# turbosound28p.net
KiCad netlist of a schematic drawn in EAGLE
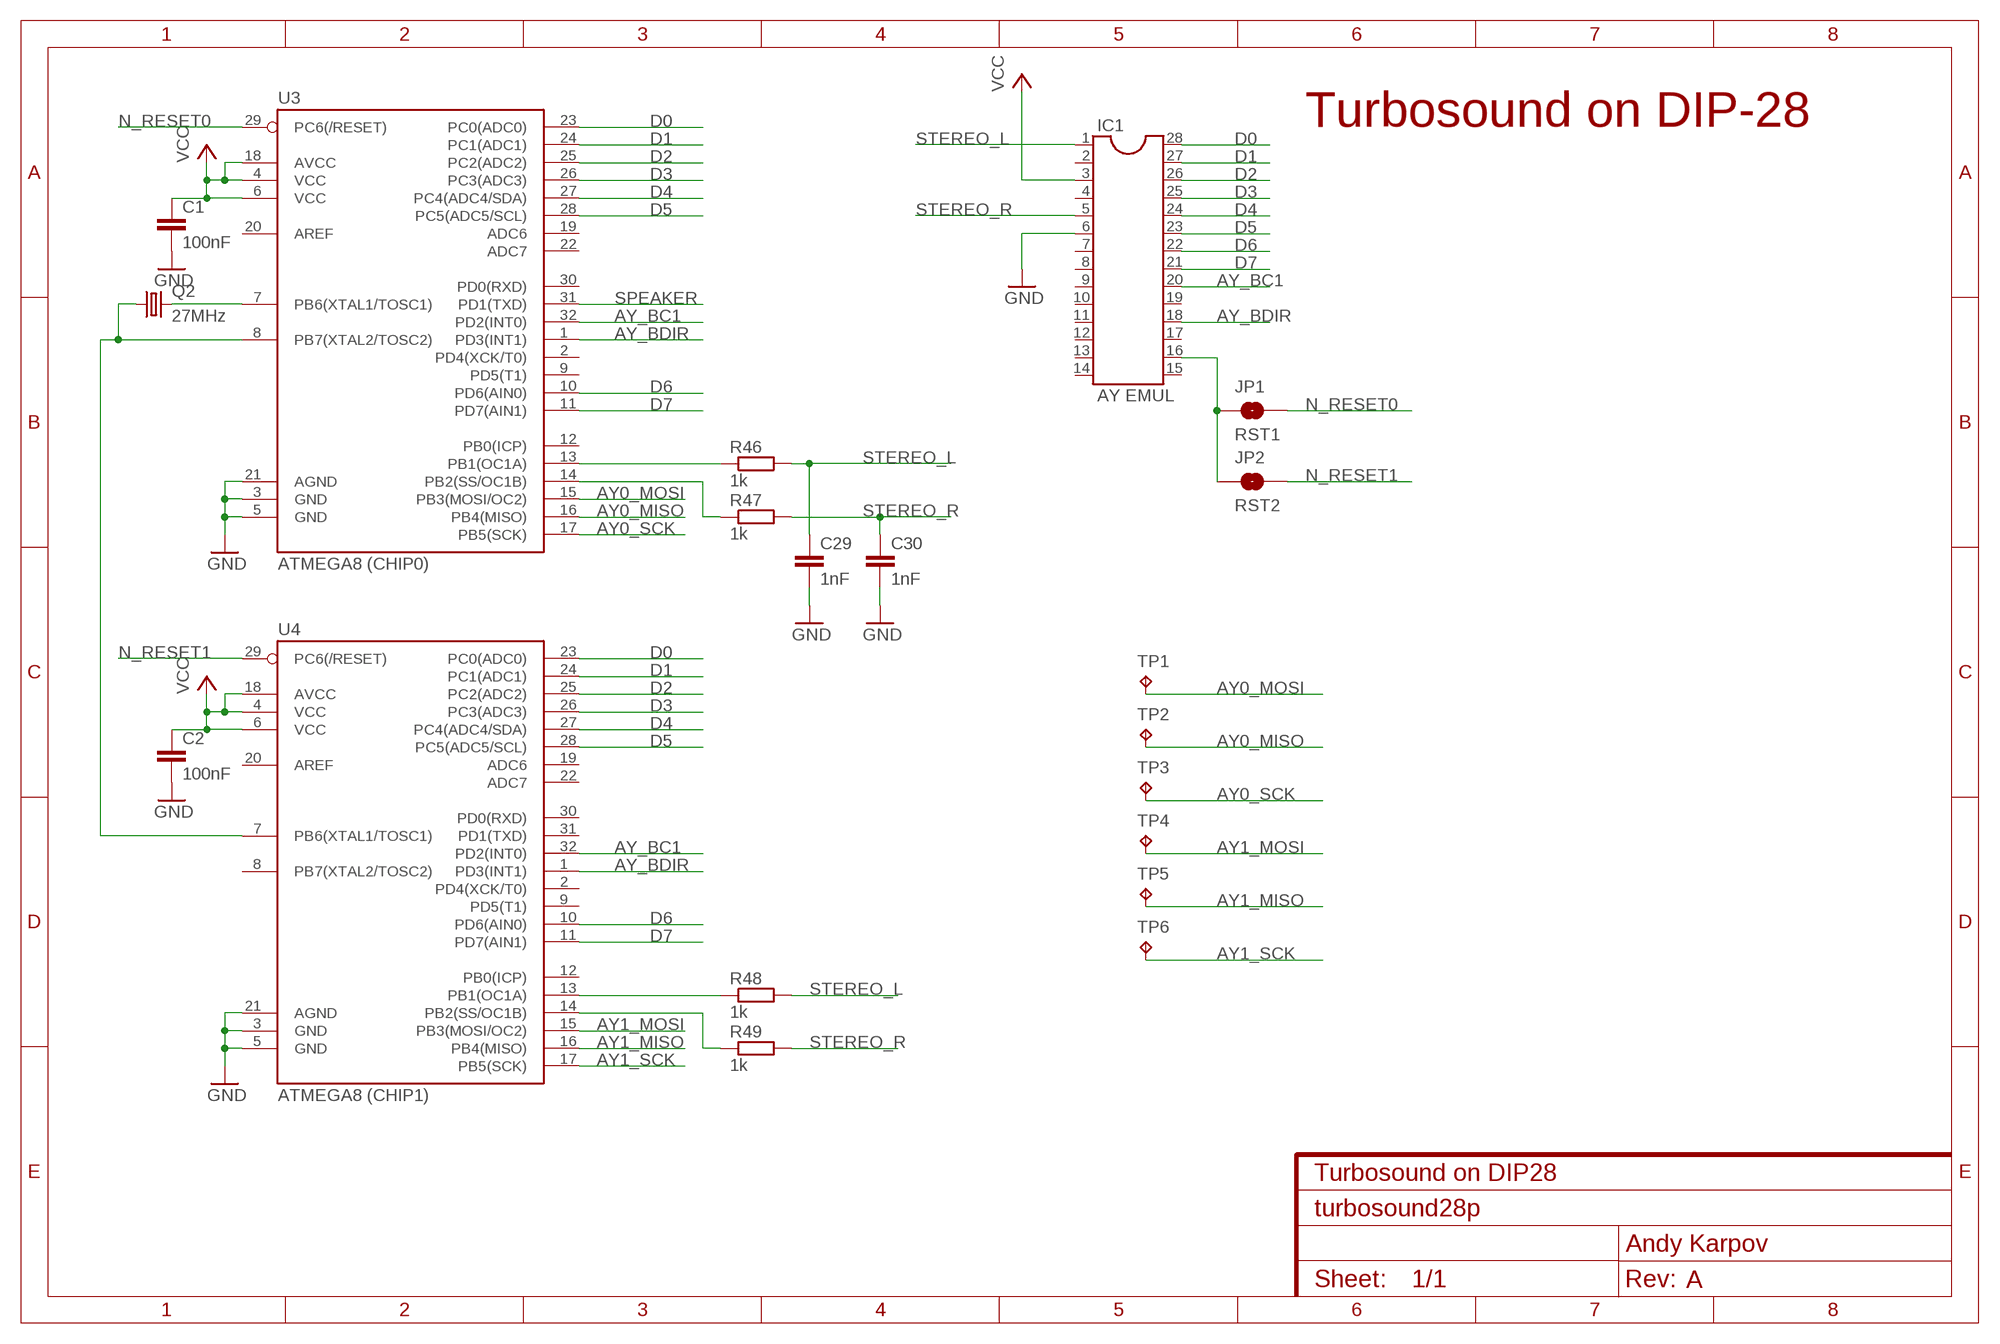
[diagram p0: schematic, sheet 1]

(export (version "E")
  (design (tool "Eeschema 10.0.6"))
  (components
    (comp (ref "C1")
      (value "100nF")
      (footprint "eagle-import:C0805")
      (libsource (lib "eagle-import") (part "C-EUC0805"))
    )
    (comp (ref "C2")
      (value "100nF")
      (footprint "eagle-import:C0805")
      (libsource (lib "eagle-import") (part "C-EUC0805"))
    )
    (comp (ref "C29")
      (value "1nF")
      (footprint "eagle-import:C0805")
      (libsource (lib "eagle-import") (part "C-EUC0805"))
    )
    (comp (ref "C30")
      (value "1nF")
      (footprint "eagle-import:C0805")
      (libsource (lib "eagle-import") (part "C-EUC0805"))
    )
    (comp (ref "IC1")
      (value "AY EMUL")
      (footprint "eagle-import:DIL28-6")
      (libsource (lib "eagle-import") (part "DIL28"))
    )
    (comp (ref "JP1")
      (value "RST1")
      (footprint "eagle-import:SMT-JUMPER_2_NO_SILK")
      (libsource (lib "eagle-import") (part "JUMPER-SMT_2_NO_SILK"))
    )
    (comp (ref "JP2")
      (value "RST2")
      (footprint "eagle-import:SMT-JUMPER_2_NO_SILK")
      (libsource (lib "eagle-import") (part "JUMPER-SMT_2_NO_SILK"))
    )
    (comp (ref "Q2")
      (value "27MHz")
      (footprint "eagle-import:HC49_S")
      (libsource (lib "eagle-import") (part "CRYSTALHC49S"))
    )
    (comp (ref "R46")
      (value "1k")
      (footprint "eagle-import:R0805")
      (libsource (lib "eagle-import") (part "R-EU_R0805"))
    )
    (comp (ref "R47")
      (value "1k")
      (footprint "eagle-import:R0805")
      (libsource (lib "eagle-import") (part "R-EU_R0805"))
    )
    (comp (ref "R48")
      (value "1k")
      (footprint "eagle-import:R0805")
      (libsource (lib "eagle-import") (part "R-EU_R0805"))
    )
    (comp (ref "R49")
      (value "1k")
      (footprint "eagle-import:R0805")
      (libsource (lib "eagle-import") (part "R-EU_R0805"))
    )
    (comp (ref "TP1")
      (value "TPB1,27")
      (footprint "eagle-import:B1,27")
      (libsource (lib "eagle-import") (part "TPB1,27"))
    )
    (comp (ref "TP2")
      (value "TPB1,27")
      (footprint "eagle-import:B1,27")
      (libsource (lib "eagle-import") (part "TPB1,27"))
    )
    (comp (ref "TP3")
      (value "TPB1,27")
      (footprint "eagle-import:B1,27")
      (libsource (lib "eagle-import") (part "TPB1,27"))
    )
    (comp (ref "TP4")
      (value "TPB1,27")
      (footprint "eagle-import:B1,27")
      (libsource (lib "eagle-import") (part "TPB1,27"))
    )
    (comp (ref "TP5")
      (value "TPB1,27")
      (footprint "eagle-import:B1,27")
      (libsource (lib "eagle-import") (part "TPB1,27"))
    )
    (comp (ref "TP6")
      (value "TPB1,27")
      (footprint "eagle-import:B1,27")
      (libsource (lib "eagle-import") (part "TPB1,27"))
    )
    (comp (ref "U3")
      (value "ATMEGA8 (CHIP0)")
      (footprint "eagle-import:TQFP32-08")
      (libsource (lib "eagle-import") (part "ATMEGA328P_TQFP"))
    )
    (comp (ref "U4")
      (value "ATMEGA8 (CHIP1)")
      (footprint "eagle-import:TQFP32-08")
      (libsource (lib "eagle-import") (part "ATMEGA328P_TQFP"))
    )
  )
  (nets
    (net (code "1") (name "/AY0_MISO") (class "Default")
      (node (ref "TP2") (pin "TP") (pinfunction "TP_TP") (pintype "input"))
      (node (ref "U3") (pin "16") (pinfunction "PB4(MISO)_16") (pintype "bidirectional"))
    )
    (net (code "2") (name "/AY0_MOSI") (class "Default")
      (node (ref "TP1") (pin "TP") (pinfunction "TP_TP") (pintype "input"))
      (node (ref "U3") (pin "15") (pinfunction "PB3(MOSI/OC2)_15") (pintype "bidirectional"))
    )
    (net (code "3") (name "/AY0_SCK") (class "Default")
      (node (ref "TP3") (pin "TP") (pinfunction "TP_TP") (pintype "input"))
      (node (ref "U3") (pin "17") (pinfunction "PB5(SCK)_17") (pintype "bidirectional"))
    )
    (net (code "4") (name "/AY1_MISO") (class "Default")
      (node (ref "TP5") (pin "TP") (pinfunction "TP_TP") (pintype "input"))
      (node (ref "U4") (pin "16") (pinfunction "PB4(MISO)_16") (pintype "bidirectional"))
    )
    (net (code "5") (name "/AY1_MOSI") (class "Default")
      (node (ref "TP4") (pin "TP") (pinfunction "TP_TP") (pintype "input"))
      (node (ref "U4") (pin "15") (pinfunction "PB3(MOSI/OC2)_15") (pintype "bidirectional"))
    )
    (net (code "6") (name "/AY1_SCK") (class "Default")
      (node (ref "TP6") (pin "TP") (pinfunction "TP_TP") (pintype "input"))
      (node (ref "U4") (pin "17") (pinfunction "PB5(SCK)_17") (pintype "bidirectional"))
    )
    (net (code "7") (name "/AY_BC1") (class "Default")
      (node (ref "IC1") (pin "20") (pinfunction "20_20") (pintype "passive"))
      (node (ref "U3") (pin "32") (pinfunction "PD2(INT0)_32") (pintype "bidirectional"))
      (node (ref "U4") (pin "32") (pinfunction "PD2(INT0)_32") (pintype "bidirectional"))
    )
    (net (code "8") (name "/AY_BDIR") (class "Default")
      (node (ref "IC1") (pin "18") (pinfunction "18_18") (pintype "passive"))
      (node (ref "U3") (pin "1") (pinfunction "PD3(INT1)_1") (pintype "bidirectional"))
      (node (ref "U4") (pin "1") (pinfunction "PD3(INT1)_1") (pintype "bidirectional"))
    )
    (net (code "9") (name "/D0") (class "Default")
      (node (ref "IC1") (pin "28") (pinfunction "28_28") (pintype "passive"))
      (node (ref "U3") (pin "23") (pinfunction "PC0(ADC0)_23") (pintype "bidirectional"))
      (node (ref "U4") (pin "23") (pinfunction "PC0(ADC0)_23") (pintype "bidirectional"))
    )
    (net (code "10") (name "/D1") (class "Default")
      (node (ref "IC1") (pin "27") (pinfunction "27_27") (pintype "passive"))
      (node (ref "U3") (pin "24") (pinfunction "PC1(ADC1)_24") (pintype "bidirectional"))
      (node (ref "U4") (pin "24") (pinfunction "PC1(ADC1)_24") (pintype "bidirectional"))
    )
    (net (code "11") (name "/D2") (class "Default")
      (node (ref "IC1") (pin "26") (pinfunction "26_26") (pintype "passive"))
      (node (ref "U3") (pin "25") (pinfunction "PC2(ADC2)_25") (pintype "bidirectional"))
      (node (ref "U4") (pin "25") (pinfunction "PC2(ADC2)_25") (pintype "bidirectional"))
    )
    (net (code "12") (name "/D3") (class "Default")
      (node (ref "IC1") (pin "25") (pinfunction "25_25") (pintype "passive"))
      (node (ref "U3") (pin "26") (pinfunction "PC3(ADC3)_26") (pintype "bidirectional"))
      (node (ref "U4") (pin "26") (pinfunction "PC3(ADC3)_26") (pintype "bidirectional"))
    )
    (net (code "13") (name "/D4") (class "Default")
      (node (ref "IC1") (pin "24") (pinfunction "24_24") (pintype "passive"))
      (node (ref "U3") (pin "27") (pinfunction "PC4(ADC4/SDA)_27") (pintype "bidirectional"))
      (node (ref "U4") (pin "27") (pinfunction "PC4(ADC4/SDA)_27") (pintype "bidirectional"))
    )
    (net (code "14") (name "/D5") (class "Default")
      (node (ref "IC1") (pin "23") (pinfunction "23_23") (pintype "passive"))
      (node (ref "U3") (pin "28") (pinfunction "PC5(ADC5/SCL)_28") (pintype "bidirectional"))
      (node (ref "U4") (pin "28") (pinfunction "PC5(ADC5/SCL)_28") (pintype "bidirectional"))
    )
    (net (code "15") (name "/D6") (class "Default")
      (node (ref "IC1") (pin "22") (pinfunction "22_22") (pintype "passive"))
      (node (ref "U3") (pin "10") (pinfunction "PD6(AIN0)_10") (pintype "bidirectional"))
      (node (ref "U4") (pin "10") (pinfunction "PD6(AIN0)_10") (pintype "bidirectional"))
    )
    (net (code "16") (name "/D7") (class "Default")
      (node (ref "IC1") (pin "21") (pinfunction "21_21") (pintype "passive"))
      (node (ref "U3") (pin "11") (pinfunction "PD7(AIN1)_11") (pintype "bidirectional"))
      (node (ref "U4") (pin "11") (pinfunction "PD7(AIN1)_11") (pintype "bidirectional"))
    )
    (net (code "17") (name "/N_RESET0") (class "Default")
      (node (ref "JP1") (pin "2") (pinfunction "2_2") (pintype "passive"))
      (node (ref "U3") (pin "29") (pinfunction "PC6(/RESET)_29") (pintype "bidirectional"))
    )
    (net (code "18") (name "/N_RESET1") (class "Default")
      (node (ref "JP2") (pin "2") (pinfunction "2_2") (pintype "passive"))
      (node (ref "U4") (pin "29") (pinfunction "PC6(/RESET)_29") (pintype "bidirectional"))
    )
    (net (code "19") (name "/SPEAKER") (class "Default")
      (node (ref "U3") (pin "31") (pinfunction "PD1(TXD)_31") (pintype "bidirectional"))
    )
    (net (code "20") (name "/STEREO_L") (class "Default")
      (node (ref "C29") (pin "1") (pinfunction "1_1") (pintype "passive"))
      (node (ref "IC1") (pin "1") (pinfunction "1_1") (pintype "passive"))
      (node (ref "R46") (pin "2") (pinfunction "2_2") (pintype "passive"))
      (node (ref "R48") (pin "2") (pinfunction "2_2") (pintype "passive"))
    )
    (net (code "21") (name "/STEREO_R") (class "Default")
      (node (ref "C30") (pin "1") (pinfunction "1_1") (pintype "passive"))
      (node (ref "IC1") (pin "5") (pinfunction "5_5") (pintype "passive"))
      (node (ref "R47") (pin "2") (pinfunction "2_2") (pintype "passive"))
      (node (ref "R49") (pin "2") (pinfunction "2_2") (pintype "passive"))
    )
    (net (code "22") (name "GND") (class "Default")
      (node (ref "C1") (pin "2") (pinfunction "2_2") (pintype "passive"))
      (node (ref "C2") (pin "2") (pinfunction "2_2") (pintype "passive"))
      (node (ref "C29") (pin "2") (pinfunction "2_2") (pintype "passive"))
      (node (ref "C30") (pin "2") (pinfunction "2_2") (pintype "passive"))
      (node (ref "IC1") (pin "6") (pinfunction "6_6") (pintype "passive"))
      (node (ref "U3") (pin "21") (pinfunction "AGND_21") (pintype "bidirectional"))
      (node (ref "U3") (pin "3") (pinfunction "GND_3") (pintype "bidirectional"))
      (node (ref "U3") (pin "5") (pinfunction "GND_5") (pintype "bidirectional"))
      (node (ref "U4") (pin "21") (pinfunction "AGND_21") (pintype "bidirectional"))
      (node (ref "U4") (pin "3") (pinfunction "GND_3") (pintype "bidirectional"))
      (node (ref "U4") (pin "5") (pinfunction "GND_5") (pintype "bidirectional"))
    )
    (net (code "23") (name "Net-(IC1-Pad16)") (class "Default")
      (node (ref "IC1") (pin "16") (pinfunction "16_16") (pintype "passive"))
      (node (ref "JP1") (pin "1") (pinfunction "1_1") (pintype "passive"))
      (node (ref "JP2") (pin "1") (pinfunction "1_1") (pintype "passive"))
    )
    (net (code "24") (name "Net-(U3-PB1(OC1A))") (class "Default")
      (node (ref "R46") (pin "1") (pinfunction "1_1") (pintype "passive"))
      (node (ref "U3") (pin "13") (pinfunction "PB1(OC1A)_13") (pintype "bidirectional"))
    )
    (net (code "25") (name "Net-(U3-PB2(SS{slash}OC1B))") (class "Default")
      (node (ref "R47") (pin "1") (pinfunction "1_1") (pintype "passive"))
      (node (ref "U3") (pin "14") (pinfunction "PB2(SS/OC1B)_14") (pintype "bidirectional"))
    )
    (net (code "26") (name "Net-(U3-PB6(XTAL1{slash}TOSC1))") (class "Default")
      (node (ref "Q2") (pin "2") (pinfunction "2_2") (pintype "passive"))
      (node (ref "U3") (pin "7") (pinfunction "PB6(XTAL1/TOSC1)_7") (pintype "bidirectional"))
    )
    (net (code "27") (name "Net-(U3-PB7(XTAL2{slash}TOSC2))") (class "Default")
      (node (ref "Q2") (pin "1") (pinfunction "1_1") (pintype "passive"))
      (node (ref "U3") (pin "8") (pinfunction "PB7(XTAL2/TOSC2)_8") (pintype "bidirectional"))
      (node (ref "U4") (pin "7") (pinfunction "PB6(XTAL1/TOSC1)_7") (pintype "bidirectional"))
    )
    (net (code "28") (name "Net-(U4-PB1(OC1A))") (class "Default")
      (node (ref "R48") (pin "1") (pinfunction "1_1") (pintype "passive"))
      (node (ref "U4") (pin "13") (pinfunction "PB1(OC1A)_13") (pintype "bidirectional"))
    )
    (net (code "29") (name "Net-(U4-PB2(SS{slash}OC1B))") (class "Default")
      (node (ref "R49") (pin "1") (pinfunction "1_1") (pintype "passive"))
      (node (ref "U4") (pin "14") (pinfunction "PB2(SS/OC1B)_14") (pintype "bidirectional"))
    )
    (net (code "30") (name "VCC") (class "Default")
      (node (ref "C1") (pin "1") (pinfunction "1_1") (pintype "passive"))
      (node (ref "C2") (pin "1") (pinfunction "1_1") (pintype "passive"))
      (node (ref "IC1") (pin "3") (pinfunction "3_3") (pintype "passive"))
      (node (ref "U3") (pin "18") (pinfunction "AVCC_18") (pintype "bidirectional"))
      (node (ref "U3") (pin "4") (pinfunction "VCC_4") (pintype "bidirectional"))
      (node (ref "U3") (pin "6") (pinfunction "VCC_6") (pintype "bidirectional"))
      (node (ref "U4") (pin "18") (pinfunction "AVCC_18") (pintype "bidirectional"))
      (node (ref "U4") (pin "4") (pinfunction "VCC_4") (pintype "bidirectional"))
      (node (ref "U4") (pin "6") (pinfunction "VCC_6") (pintype "bidirectional"))
    )
    (net (code "31") (name "unconnected-(IC1-Pad2)") (class "Default")
      (node (ref "IC1") (pin "2") (pinfunction "2_2") (pintype "passive"))
    )
    (net (code "32") (name "unconnected-(IC1-Pad4)") (class "Default")
      (node (ref "IC1") (pin "4") (pinfunction "4_4") (pintype "passive"))
    )
    (net (code "33") (name "unconnected-(IC1-Pad7)") (class "Default")
      (node (ref "IC1") (pin "7") (pinfunction "7_7") (pintype "passive"))
    )
    (net (code "34") (name "unconnected-(IC1-Pad8)") (class "Default")
      (node (ref "IC1") (pin "8") (pinfunction "8_8") (pintype "passive"))
    )
    (net (code "35") (name "unconnected-(IC1-Pad9)") (class "Default")
      (node (ref "IC1") (pin "9") (pinfunction "9_9") (pintype "passive"))
    )
    (net (code "36") (name "unconnected-(IC1-Pad10)") (class "Default")
      (node (ref "IC1") (pin "10") (pinfunction "10_10") (pintype "passive"))
    )
    (net (code "37") (name "unconnected-(IC1-Pad11)") (class "Default")
      (node (ref "IC1") (pin "11") (pinfunction "11_11") (pintype "passive"))
    )
    (net (code "38") (name "unconnected-(IC1-Pad12)") (class "Default")
      (node (ref "IC1") (pin "12") (pinfunction "12_12") (pintype "passive"))
    )
    (net (code "39") (name "unconnected-(IC1-Pad13)") (class "Default")
      (node (ref "IC1") (pin "13") (pinfunction "13_13") (pintype "passive"))
    )
    (net (code "40") (name "unconnected-(IC1-Pad14)") (class "Default")
      (node (ref "IC1") (pin "14") (pinfunction "14_14") (pintype "passive"))
    )
    (net (code "41") (name "unconnected-(IC1-Pad15)") (class "Default")
      (node (ref "IC1") (pin "15") (pinfunction "15_15") (pintype "passive"))
    )
    (net (code "42") (name "unconnected-(IC1-Pad17)") (class "Default")
      (node (ref "IC1") (pin "17") (pinfunction "17_17") (pintype "passive"))
    )
    (net (code "43") (name "unconnected-(IC1-Pad19)") (class "Default")
      (node (ref "IC1") (pin "19") (pinfunction "19_19") (pintype "passive"))
    )
    (net (code "44") (name "unconnected-(U3-ADC6-Pad19)") (class "Default")
      (node (ref "U3") (pin "19") (pinfunction "ADC6_19") (pintype "bidirectional"))
    )
    (net (code "45") (name "unconnected-(U3-ADC7-Pad22)") (class "Default")
      (node (ref "U3") (pin "22") (pinfunction "ADC7_22") (pintype "bidirectional"))
    )
    (net (code "46") (name "unconnected-(U3-AREF-Pad20)") (class "Default")
      (node (ref "U3") (pin "20") (pinfunction "AREF_20") (pintype "bidirectional"))
    )
    (net (code "47") (name "unconnected-(U3-PB0(ICP)-Pad12)") (class "Default")
      (node (ref "U3") (pin "12") (pinfunction "PB0(ICP)_12") (pintype "bidirectional"))
    )
    (net (code "48") (name "unconnected-(U3-PD0(RXD)-Pad30)") (class "Default")
      (node (ref "U3") (pin "30") (pinfunction "PD0(RXD)_30") (pintype "bidirectional"))
    )
    (net (code "49") (name "unconnected-(U3-PD4(XCK{slash}T0)-Pad2)") (class "Default")
      (node (ref "U3") (pin "2") (pinfunction "PD4(XCK/T0)_2") (pintype "bidirectional"))
    )
    (net (code "50") (name "unconnected-(U3-PD5(T1)-Pad9)") (class "Default")
      (node (ref "U3") (pin "9") (pinfunction "PD5(T1)_9") (pintype "bidirectional"))
    )
    (net (code "51") (name "unconnected-(U4-ADC6-Pad19)") (class "Default")
      (node (ref "U4") (pin "19") (pinfunction "ADC6_19") (pintype "bidirectional"))
    )
    (net (code "52") (name "unconnected-(U4-ADC7-Pad22)") (class "Default")
      (node (ref "U4") (pin "22") (pinfunction "ADC7_22") (pintype "bidirectional"))
    )
    (net (code "53") (name "unconnected-(U4-AREF-Pad20)") (class "Default")
      (node (ref "U4") (pin "20") (pinfunction "AREF_20") (pintype "bidirectional"))
    )
    (net (code "54") (name "unconnected-(U4-PB0(ICP)-Pad12)") (class "Default")
      (node (ref "U4") (pin "12") (pinfunction "PB0(ICP)_12") (pintype "bidirectional"))
    )
    (net (code "55") (name "unconnected-(U4-PB7(XTAL2{slash}TOSC2)-Pad8)") (class "Default")
      (node (ref "U4") (pin "8") (pinfunction "PB7(XTAL2/TOSC2)_8") (pintype "bidirectional"))
    )
    (net (code "56") (name "unconnected-(U4-PD0(RXD)-Pad30)") (class "Default")
      (node (ref "U4") (pin "30") (pinfunction "PD0(RXD)_30") (pintype "bidirectional"))
    )
    (net (code "57") (name "unconnected-(U4-PD1(TXD)-Pad31)") (class "Default")
      (node (ref "U4") (pin "31") (pinfunction "PD1(TXD)_31") (pintype "bidirectional"))
    )
    (net (code "58") (name "unconnected-(U4-PD4(XCK{slash}T0)-Pad2)") (class "Default")
      (node (ref "U4") (pin "2") (pinfunction "PD4(XCK/T0)_2") (pintype "bidirectional"))
    )
    (net (code "59") (name "unconnected-(U4-PD5(T1)-Pad9)") (class "Default")
      (node (ref "U4") (pin "9") (pinfunction "PD5(T1)_9") (pintype "bidirectional"))
    )
  )
)
